# ZYNQ_DDR3_Bank_502.net
KiCad netlist of a schematic drawn in Altium Designer
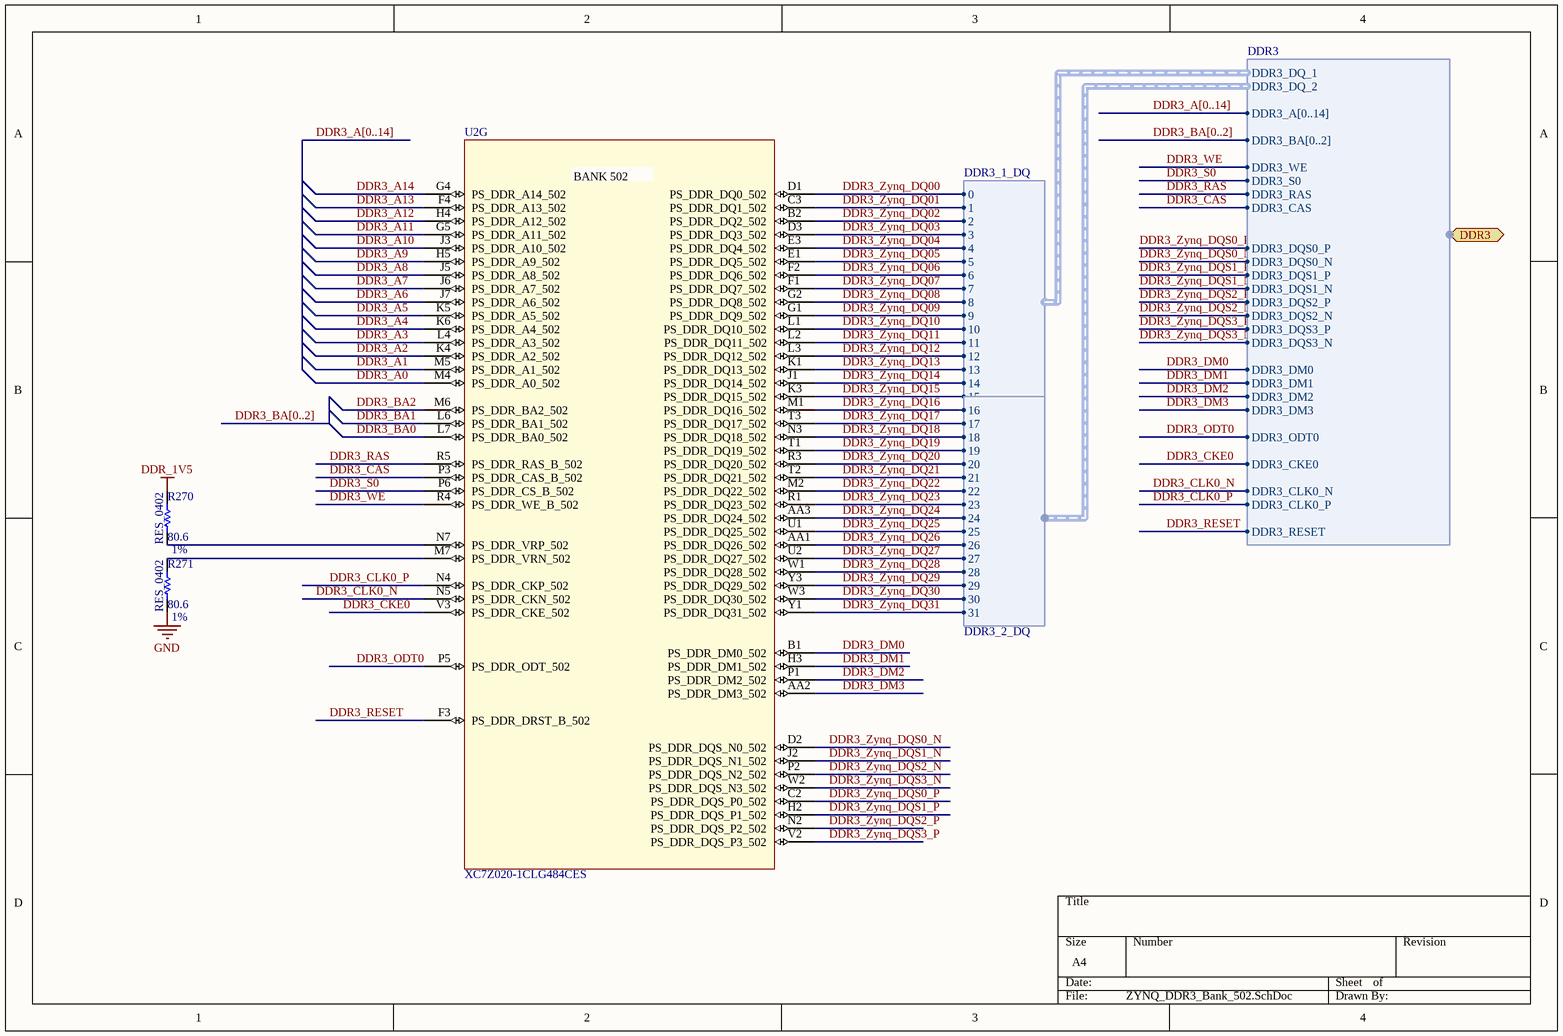
[diagram p0: ZYNQ_DDR3_Bank_502.SchDoc]

(export (version "E")
  (design (tool "Eeschema 10.0.6"))
  (components
    (comp (ref "R270")
      (value "RES_0402")
      (footprint "RESC0402(1005)_N")
      (description "80.6 ohm, 1% 1/16W, 0402")
      (fields
        (field (name "ALTIUM_VALUE") "80.6")
        (field (name "TOLERANCE") "1%")
        (field (name "PART NUMBER") "RMCF0402FT80R6")
        (field (name "MANUFACTURER") "Stackpole Electronics")
      )
      (libsource (lib "COMRAD_Database") (part "RES_0402"))
    )
    (comp (ref "R271")
      (value "RES_0402")
      (footprint "RESC0402(1005)_N")
      (description "80.6 ohm, 1% 1/16W, 0402")
      (fields
        (field (name "ALTIUM_VALUE") "80.6")
        (field (name "TOLERANCE") "1%")
        (field (name "PART NUMBER") "RMCF0402FT80R6")
        (field (name "MANUFACTURER") "Stackpole Electronics")
      )
      (libsource (lib "COMRAD_Database") (part "RES_0402"))
    )
    (comp (ref "U2")
      (value "XC7Z020-1CLG484CES")
      (footprint "ZYNQ_xc7z020clg484pkg_BGA-484")
      (description "XC7Z020-1CLG484CES, Zynq-7000 All Programmable SoC")
      (fields (field (name "MANUFACTURER") "Xilinx"))
      (libsource (lib "COMRAD_Database") (part "ZYNQ_XC7Z020CLG484PKG"))
    )
  )
  (nets
    (net (code "4") (name "/DDR3_A0") (class "Default")
      (node (ref "U2") (pin "M4") (pinfunction "PS_DDR_A0_502_M4") (pintype "bidirectional"))
    )
    (net (code "5") (name "/DDR3_A1") (class "Default")
      (node (ref "U2") (pin "M5") (pinfunction "PS_DDR_A1_502_M5") (pintype "bidirectional"))
    )
    (net (code "6") (name "/DDR3_A2") (class "Default")
      (node (ref "U2") (pin "K4") (pinfunction "PS_DDR_A2_502_K4") (pintype "bidirectional"))
    )
    (net (code "7") (name "/DDR3_A3") (class "Default")
      (node (ref "U2") (pin "L4") (pinfunction "PS_DDR_A3_502_L4") (pintype "bidirectional"))
    )
    (net (code "8") (name "/DDR3_A4") (class "Default")
      (node (ref "U2") (pin "K6") (pinfunction "PS_DDR_A4_502_K6") (pintype "bidirectional"))
    )
    (net (code "9") (name "/DDR3_A5") (class "Default")
      (node (ref "U2") (pin "K5") (pinfunction "PS_DDR_A5_502_K5") (pintype "bidirectional"))
    )
    (net (code "10") (name "/DDR3_A6") (class "Default")
      (node (ref "U2") (pin "J7") (pinfunction "PS_DDR_A6_502_J7") (pintype "bidirectional"))
    )
    (net (code "11") (name "/DDR3_A7") (class "Default")
      (node (ref "U2") (pin "J6") (pinfunction "PS_DDR_A7_502_J6") (pintype "bidirectional"))
    )
    (net (code "12") (name "/DDR3_A8") (class "Default")
      (node (ref "U2") (pin "J5") (pinfunction "PS_DDR_A8_502_J5") (pintype "bidirectional"))
    )
    (net (code "13") (name "/DDR3_A9") (class "Default")
      (node (ref "U2") (pin "H5") (pinfunction "PS_DDR_A9_502_H5") (pintype "bidirectional"))
    )
    (net (code "14") (name "/DDR3_A10") (class "Default")
      (node (ref "U2") (pin "J3") (pinfunction "PS_DDR_A10_502_J3") (pintype "bidirectional"))
    )
    (net (code "15") (name "/DDR3_A11") (class "Default")
      (node (ref "U2") (pin "G5") (pinfunction "PS_DDR_A11_502_G5") (pintype "bidirectional"))
    )
    (net (code "16") (name "/DDR3_A12") (class "Default")
      (node (ref "U2") (pin "H4") (pinfunction "PS_DDR_A12_502_H4") (pintype "bidirectional"))
    )
    (net (code "17") (name "/DDR3_A13") (class "Default")
      (node (ref "U2") (pin "F4") (pinfunction "PS_DDR_A13_502_F4") (pintype "bidirectional"))
    )
    (net (code "18") (name "/DDR3_A14") (class "Default")
      (node (ref "U2") (pin "G4") (pinfunction "PS_DDR_A14_502_G4") (pintype "bidirectional"))
    )
    (net (code "20") (name "/DDR3_BA0") (class "Default")
      (node (ref "U2") (pin "L7") (pinfunction "PS_DDR_BA0_502_L7") (pintype "bidirectional"))
    )
    (net (code "21") (name "/DDR3_BA1") (class "Default")
      (node (ref "U2") (pin "L6") (pinfunction "PS_DDR_BA1_502_L6") (pintype "bidirectional"))
    )
    (net (code "22") (name "/DDR3_BA2") (class "Default")
      (node (ref "U2") (pin "M6") (pinfunction "PS_DDR_BA2_502_M6") (pintype "bidirectional"))
    )
    (net (code "24") (name "/DDR3_CAS") (class "Default")
      (node (ref "U2") (pin "P3") (pinfunction "PS_DDR_CAS_B_502_P3") (pintype "bidirectional"))
    )
    (net (code "25") (name "/DDR3_CKE0") (class "Default")
      (node (ref "U2") (pin "V3") (pinfunction "PS_DDR_CKE_502_V3") (pintype "bidirectional"))
    )
    (net (code "26") (name "/DDR3_CLK0_N") (class "Default")
      (node (ref "U2") (pin "N5") (pinfunction "PS_DDR_CKN_502_N5") (pintype "bidirectional"))
    )
    (net (code "27") (name "/DDR3_CLK0_P") (class "Default")
      (node (ref "U2") (pin "N4") (pinfunction "PS_DDR_CKP_502_N4") (pintype "bidirectional"))
    )
    (net (code "28") (name "/DDR3_DM0") (class "Default")
      (node (ref "U2") (pin "B1") (pinfunction "PS_DDR_DM0_502_B1") (pintype "bidirectional"))
    )
    (net (code "29") (name "/DDR3_DM1") (class "Default")
      (node (ref "U2") (pin "H3") (pinfunction "PS_DDR_DM1_502_H3") (pintype "bidirectional"))
    )
    (net (code "30") (name "/DDR3_DM2") (class "Default")
      (node (ref "U2") (pin "P1") (pinfunction "PS_DDR_DM2_502_P1") (pintype "bidirectional"))
    )
    (net (code "31") (name "/DDR3_DM3") (class "Default")
      (node (ref "U2") (pin "AA2") (pinfunction "PS_DDR_DM3_502_AA2") (pintype "bidirectional"))
    )
    (net (code "32") (name "/DDR3_ODT0") (class "Default")
      (node (ref "U2") (pin "P5") (pinfunction "PS_DDR_ODT_502_P5") (pintype "bidirectional"))
    )
    (net (code "33") (name "/DDR3_RAS") (class "Default")
      (node (ref "U2") (pin "R5") (pinfunction "PS_DDR_RAS_B_502_R5") (pintype "bidirectional"))
    )
    (net (code "34") (name "/DDR3_RESET") (class "Default")
      (node (ref "U2") (pin "F3") (pinfunction "PS_DDR_DRST_B_502_F3") (pintype "bidirectional"))
    )
    (net (code "35") (name "/DDR3_S0") (class "Default")
      (node (ref "U2") (pin "P6") (pinfunction "PS_DDR_CS_B_502_P6") (pintype "bidirectional"))
    )
    (net (code "36") (name "/DDR3_WE") (class "Default")
      (node (ref "U2") (pin "R4") (pinfunction "PS_DDR_WE_B_502_R4") (pintype "bidirectional"))
    )
    (net (code "37") (name "/DDR3_Zynq_DQ00") (class "Default")
      (node (ref "U2") (pin "D1") (pinfunction "PS_DDR_DQ0_502_D1") (pintype "bidirectional"))
    )
    (net (code "38") (name "/DDR3_Zynq_DQ01") (class "Default")
      (node (ref "U2") (pin "C3") (pinfunction "PS_DDR_DQ1_502_C3") (pintype "bidirectional"))
    )
    (net (code "39") (name "/DDR3_Zynq_DQ02") (class "Default")
      (node (ref "U2") (pin "B2") (pinfunction "PS_DDR_DQ2_502_B2") (pintype "bidirectional"))
    )
    (net (code "40") (name "/DDR3_Zynq_DQ03") (class "Default")
      (node (ref "U2") (pin "D3") (pinfunction "PS_DDR_DQ3_502_D3") (pintype "bidirectional"))
    )
    (net (code "41") (name "/DDR3_Zynq_DQ04") (class "Default")
      (node (ref "U2") (pin "E3") (pinfunction "PS_DDR_DQ4_502_E3") (pintype "bidirectional"))
    )
    (net (code "42") (name "/DDR3_Zynq_DQ05") (class "Default")
      (node (ref "U2") (pin "E1") (pinfunction "PS_DDR_DQ5_502_E1") (pintype "bidirectional"))
    )
    (net (code "43") (name "/DDR3_Zynq_DQ06") (class "Default")
      (node (ref "U2") (pin "F2") (pinfunction "PS_DDR_DQ6_502_F2") (pintype "bidirectional"))
    )
    (net (code "44") (name "/DDR3_Zynq_DQ07") (class "Default")
      (node (ref "U2") (pin "F1") (pinfunction "PS_DDR_DQ7_502_F1") (pintype "bidirectional"))
    )
    (net (code "45") (name "/DDR3_Zynq_DQ08") (class "Default")
      (node (ref "U2") (pin "G2") (pinfunction "PS_DDR_DQ8_502_G2") (pintype "bidirectional"))
    )
    (net (code "46") (name "/DDR3_Zynq_DQ09") (class "Default")
      (node (ref "U2") (pin "G1") (pinfunction "PS_DDR_DQ9_502_G1") (pintype "bidirectional"))
    )
    (net (code "47") (name "/DDR3_Zynq_DQ10") (class "Default")
      (node (ref "U2") (pin "L1") (pinfunction "PS_DDR_DQ10_502_L1") (pintype "bidirectional"))
    )
    (net (code "48") (name "/DDR3_Zynq_DQ11") (class "Default")
      (node (ref "U2") (pin "L2") (pinfunction "PS_DDR_DQ11_502_L2") (pintype "bidirectional"))
    )
    (net (code "49") (name "/DDR3_Zynq_DQ12") (class "Default")
      (node (ref "U2") (pin "L3") (pinfunction "PS_DDR_DQ12_502_L3") (pintype "bidirectional"))
    )
    (net (code "50") (name "/DDR3_Zynq_DQ13") (class "Default")
      (node (ref "U2") (pin "K1") (pinfunction "PS_DDR_DQ13_502_K1") (pintype "bidirectional"))
    )
    (net (code "51") (name "/DDR3_Zynq_DQ14") (class "Default")
      (node (ref "U2") (pin "J1") (pinfunction "PS_DDR_DQ14_502_J1") (pintype "bidirectional"))
    )
    (net (code "52") (name "/DDR3_Zynq_DQ15") (class "Default")
      (node (ref "U2") (pin "K3") (pinfunction "PS_DDR_DQ15_502_K3") (pintype "bidirectional"))
    )
    (net (code "53") (name "/DDR3_Zynq_DQ16") (class "Default")
      (node (ref "U2") (pin "M1") (pinfunction "PS_DDR_DQ16_502_M1") (pintype "bidirectional"))
    )
    (net (code "54") (name "/DDR3_Zynq_DQ17") (class "Default")
      (node (ref "U2") (pin "T3") (pinfunction "PS_DDR_DQ17_502_T3") (pintype "bidirectional"))
    )
    (net (code "55") (name "/DDR3_Zynq_DQ18") (class "Default")
      (node (ref "U2") (pin "N3") (pinfunction "PS_DDR_DQ18_502_N3") (pintype "bidirectional"))
    )
    (net (code "56") (name "/DDR3_Zynq_DQ19") (class "Default")
      (node (ref "U2") (pin "T1") (pinfunction "PS_DDR_DQ19_502_T1") (pintype "bidirectional"))
    )
    (net (code "57") (name "/DDR3_Zynq_DQ20") (class "Default")
      (node (ref "U2") (pin "R3") (pinfunction "PS_DDR_DQ20_502_R3") (pintype "bidirectional"))
    )
    (net (code "58") (name "/DDR3_Zynq_DQ21") (class "Default")
      (node (ref "U2") (pin "T2") (pinfunction "PS_DDR_DQ21_502_T2") (pintype "bidirectional"))
    )
    (net (code "59") (name "/DDR3_Zynq_DQ22") (class "Default")
      (node (ref "U2") (pin "M2") (pinfunction "PS_DDR_DQ22_502_M2") (pintype "bidirectional"))
    )
    (net (code "60") (name "/DDR3_Zynq_DQ23") (class "Default")
      (node (ref "U2") (pin "R1") (pinfunction "PS_DDR_DQ23_502_R1") (pintype "bidirectional"))
    )
    (net (code "61") (name "/DDR3_Zynq_DQ24") (class "Default")
      (node (ref "U2") (pin "AA3") (pinfunction "PS_DDR_DQ24_502_AA3") (pintype "bidirectional"))
    )
    (net (code "62") (name "/DDR3_Zynq_DQ25") (class "Default")
      (node (ref "U2") (pin "U1") (pinfunction "PS_DDR_DQ25_502_U1") (pintype "bidirectional"))
    )
    (net (code "63") (name "/DDR3_Zynq_DQ26") (class "Default")
      (node (ref "U2") (pin "AA1") (pinfunction "PS_DDR_DQ26_502_AA1") (pintype "bidirectional"))
    )
    (net (code "64") (name "/DDR3_Zynq_DQ27") (class "Default")
      (node (ref "U2") (pin "U2") (pinfunction "PS_DDR_DQ27_502_U2") (pintype "bidirectional"))
    )
    (net (code "65") (name "/DDR3_Zynq_DQ28") (class "Default")
      (node (ref "U2") (pin "W1") (pinfunction "PS_DDR_DQ28_502_W1") (pintype "bidirectional"))
    )
    (net (code "66") (name "/DDR3_Zynq_DQ29") (class "Default")
      (node (ref "U2") (pin "Y3") (pinfunction "PS_DDR_DQ29_502_Y3") (pintype "bidirectional"))
    )
    (net (code "67") (name "/DDR3_Zynq_DQ30") (class "Default")
      (node (ref "U2") (pin "W3") (pinfunction "PS_DDR_DQ30_502_W3") (pintype "bidirectional"))
    )
    (net (code "68") (name "/DDR3_Zynq_DQ31") (class "Default")
      (node (ref "U2") (pin "Y1") (pinfunction "PS_DDR_DQ31_502_Y1") (pintype "bidirectional"))
    )
    (net (code "69") (name "/DDR3_Zynq_DQS0_N") (class "Default")
      (node (ref "U2") (pin "D2") (pinfunction "PS_DDR_DQS_N0_502_D2") (pintype "bidirectional"))
    )
    (net (code "70") (name "/DDR3_Zynq_DQS0_P") (class "Default")
      (node (ref "U2") (pin "C2") (pinfunction "PS_DDR_DQS_P0_502_C2") (pintype "bidirectional"))
    )
    (net (code "71") (name "/DDR3_Zynq_DQS1_N") (class "Default")
      (node (ref "U2") (pin "J2") (pinfunction "PS_DDR_DQS_N1_502_J2") (pintype "bidirectional"))
    )
    (net (code "72") (name "/DDR3_Zynq_DQS1_P") (class "Default")
      (node (ref "U2") (pin "H2") (pinfunction "PS_DDR_DQS_P1_502_H2") (pintype "bidirectional"))
    )
    (net (code "73") (name "/DDR3_Zynq_DQS2_N") (class "Default")
      (node (ref "U2") (pin "P2") (pinfunction "PS_DDR_DQS_N2_502_P2") (pintype "bidirectional"))
    )
    (net (code "74") (name "/DDR3_Zynq_DQS2_P") (class "Default")
      (node (ref "U2") (pin "N2") (pinfunction "PS_DDR_DQS_P2_502_N2") (pintype "bidirectional"))
    )
    (net (code "75") (name "/DDR3_Zynq_DQS3_N") (class "Default")
      (node (ref "U2") (pin "W2") (pinfunction "PS_DDR_DQS_N3_502_W2") (pintype "bidirectional"))
    )
    (net (code "76") (name "/DDR3_Zynq_DQS3_P") (class "Default")
      (node (ref "U2") (pin "V2") (pinfunction "PS_DDR_DQS_P3_502_V2") (pintype "bidirectional"))
    )
    (net (code "81") (name "DDR_1V5") (class "Default")
      (node (ref "R270") (pin "2") (pinfunction "2_2") (pintype "passive"))
    )
    (net (code "82") (name "GND") (class "Default")
      (node (ref "R271") (pin "1") (pinfunction "1_1") (pintype "passive"))
    )
    (net (code "83") (name "Net-(U2G-PS_DDR_VRN_502)") (class "Default")
      (node (ref "R271") (pin "2") (pinfunction "2_2") (pintype "passive"))
      (node (ref "U2") (pin "M7") (pinfunction "PS_DDR_VRN_502_M7") (pintype "bidirectional"))
    )
    (net (code "84") (name "Net-(U2G-PS_DDR_VRP_502)") (class "Default")
      (node (ref "R270") (pin "1") (pinfunction "1_1") (pintype "passive"))
      (node (ref "U2") (pin "N7") (pinfunction "PS_DDR_VRP_502_N7") (pintype "bidirectional"))
    )
  )
)
